# 2_P2_schdoc.net
KiCad netlist of a schematic drawn in Altium Designer
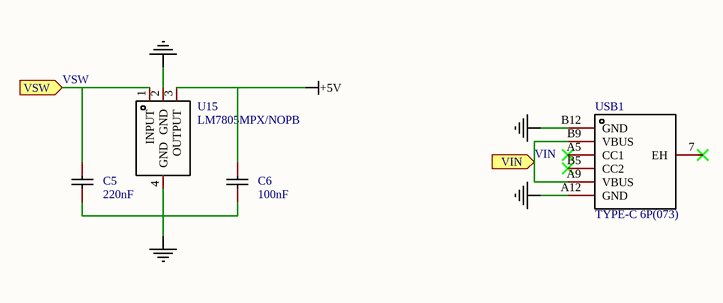
[diagram p0: 2_P2.schdoc.schdoc]

(export (version "E")
  (design (tool "Eeschema 10.0.6"))
  (components
    (comp (ref "C5")
      (value "220nF")
      (fields
        (field (name "NAME") "220nF")
        (field (name "MANUFACTURER PART") "CL21B224KBFNNNE")
        (field (name "MANUFACTURER") "SAMSUNG(三星)")
        (field (name "TOLERANCE") "±10%")
      )
      (libsource (lib "altium-import") (part "root_1_CL21B224KBFNNNE_"))
    )
    (comp (ref "C6")
      (value "100nF")
      (fields
        (field (name "NAME") "100nF")
        (field (name "MANUFACTURER") "YAGEO(国巨)")
        (field (name "MANUFACTURER PART") "CC0805KRX7R9BB104")
        (field (name "TOLERANCE") "±10%")
      )
      (libsource (lib "altium-import") (part "root_1_CC0805KRX7R9BB104_"))
    )
    (comp (ref "U15")
      (value "LM7805MPX/NOPB")
      (description "输出类型:固定;最大输入电压:35V;输出电压:5V;最大输出电流:1.5A;电源纹波抑制比(PSRR):80dB@(120Hz);输出极性:正极;")
      (fields (field (name "NAME") "LM7805MPX/NOPB") (field (name "MANUFACTURER") "TI(德州仪器)"))
      (libsource (lib "altium-import") (part "root_3_mirrored_LM7805MPX/NOPB_"))
    )
    (comp (ref "USB1")
      (value "TYPE-C 6P(073)")
      (description "连接器类型:Type-C;标准:-;公母:母;端口数量:1;触点数量:6P;安装方式:卧贴;额定电流 - 电源:5A;工作温度范围:-25℃~+85℃;")
      (fields (field (name "NAME") "TYPE-C 6P(073)") (field (name "MANUFACTURER") "SHOU HAN(首韩)"))
      (libsource (lib "altium-import") (part "root_0_TYPE-C 6P(073)_"))
    )
  )
  (nets
    (net (code "1") (name "+5V") (class "Default")
      (node (ref "C6") (pin "2") (pinfunction "2_2") (pintype "passive"))
      (node (ref "U15") (pin "3") (pinfunction "OUTPUT_3") (pintype "passive"))
    )
    (net (code "2") (name "/VIN") (class "Default")
      (node (ref "USB1") (pin "A9") (pinfunction "VBUS_A9") (pintype "passive"))
      (node (ref "USB1") (pin "B9") (pinfunction "VBUS_B9") (pintype "passive"))
    )
    (net (code "3") (name "/VSW") (class "Default")
      (node (ref "C5") (pin "2") (pinfunction "2_2") (pintype "passive"))
      (node (ref "U15") (pin "1") (pinfunction "INPUT_1") (pintype "passive"))
    )
    (net (code "4") (name "<NO NET>") (class "Default")
      (node (ref "C5") (pin "1") (pinfunction "1_1") (pintype "passive"))
      (node (ref "C6") (pin "1") (pinfunction "1_1") (pintype "passive"))
      (node (ref "U15") (pin "2") (pinfunction "GND_2") (pintype "passive"))
      (node (ref "U15") (pin "4") (pinfunction "GND_4") (pintype "passive"))
      (node (ref "USB1") (pin "A12") (pinfunction "GND_A12") (pintype "passive"))
      (node (ref "USB1") (pin "B12") (pinfunction "GND_B12") (pintype "passive"))
    )
    (net (code "5") (name "unconnected-(USB1-CC1-PadA5)") (class "Default")
      (node (ref "USB1") (pin "A5") (pinfunction "CC1_A5") (pintype "passive+no_connect"))
    )
    (net (code "6") (name "unconnected-(USB1-CC2-PadB5)") (class "Default")
      (node (ref "USB1") (pin "B5") (pinfunction "CC2_B5") (pintype "passive+no_connect"))
    )
    (net (code "7") (name "unconnected-(USB1-EH-Pad7)") (class "Default")
      (node (ref "USB1") (pin "7") (pinfunction "EH_7") (pintype "passive+no_connect"))
    )
  )
)
